# DigitalOutLED-02.net
KiCad netlist of a schematic drawn in EAGLE
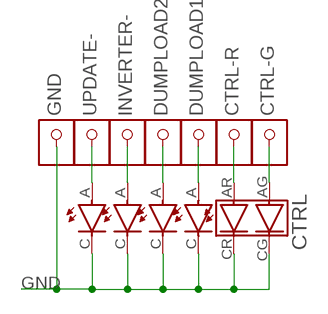
[diagram p0: schematic, sheet 1]

(export (version "E")
  (design (tool "Eeschema 10.0.6"))
  (components
    (comp (ref "CTRL")
      (value "PLCC4-RG")
      (footprint "eagle-import:PLCC4")
      (libsource (lib "eagle-import") (part "PLCC4-RG"))
    )
    (comp (ref "CTRL-G")
      (value "1X1HEADER")
      (footprint "eagle-import:1X1HEADER")
      (libsource (lib "eagle-import") (part "1X1HEADER"))
    )
    (comp (ref "CTRL-R")
      (value "1X1HEADER")
      (footprint "eagle-import:1X1HEADER")
      (libsource (lib "eagle-import") (part "1X1HEADER"))
    )
    (comp (ref "DL1")
      (value "PLCC2")
      (footprint "eagle-import:PLCC2")
      (libsource (lib "eagle-import") (part "PLCC2"))
    )
    (comp (ref "DL2")
      (value "PLCC2")
      (footprint "eagle-import:PLCC2")
      (libsource (lib "eagle-import") (part "PLCC2"))
    )
    (comp (ref "DUMPLOAD1")
      (value "1X1HEADER")
      (footprint "eagle-import:1X1HEADER")
      (libsource (lib "eagle-import") (part "1X1HEADER"))
    )
    (comp (ref "DUMPLOAD2")
      (value "1X1HEADER")
      (footprint "eagle-import:1X1HEADER")
      (libsource (lib "eagle-import") (part "1X1HEADER"))
    )
    (comp (ref "GND")
      (value "1X1HEADER")
      (footprint "eagle-import:1X1HEADER")
      (libsource (lib "eagle-import") (part "1X1HEADER"))
    )
    (comp (ref "INVERTER")
      (value "PLCC2")
      (footprint "eagle-import:PLCC2")
      (libsource (lib "eagle-import") (part "PLCC2"))
    )
    (comp (ref "INVERTER-")
      (value "1X1HEADER")
      (footprint "eagle-import:1X1HEADER")
      (libsource (lib "eagle-import") (part "1X1HEADER"))
    )
    (comp (ref "UPDATE")
      (value "PLCC2")
      (footprint "eagle-import:PLCC2")
      (libsource (lib "eagle-import") (part "PLCC2"))
    )
    (comp (ref "UPDATE-")
      (value "1X1HEADER")
      (footprint "eagle-import:1X1HEADER")
      (libsource (lib "eagle-import") (part "1X1HEADER"))
    )
  )
  (nets
    (net (code "1") (name "/GND") (class "Default")
      (node (ref "CTRL") (pin "CG") (pinfunction "CG_CG") (pintype "bidirectional"))
      (node (ref "CTRL") (pin "CR") (pinfunction "CR_CR") (pintype "bidirectional"))
      (node (ref "DL1") (pin "C") (pinfunction "C_C") (pintype "bidirectional"))
      (node (ref "DL2") (pin "C") (pinfunction "C_C") (pintype "bidirectional"))
      (node (ref "GND") (pin "P$1") (pinfunction "1_P$1") (pintype "bidirectional"))
      (node (ref "INVERTER") (pin "C") (pinfunction "C_C") (pintype "bidirectional"))
      (node (ref "UPDATE") (pin "C") (pinfunction "C_C") (pintype "bidirectional"))
    )
    (net (code "2") (name "Net-(CTRL-G-1)") (class "Default")
      (node (ref "CTRL") (pin "AG") (pinfunction "AG_AG") (pintype "bidirectional"))
      (node (ref "CTRL-G") (pin "P$1") (pinfunction "1_P$1") (pintype "bidirectional"))
    )
    (net (code "3") (name "Net-(CTRL-R-1)") (class "Default")
      (node (ref "CTRL") (pin "AR") (pinfunction "AR_AR") (pintype "bidirectional"))
      (node (ref "CTRL-R") (pin "P$1") (pinfunction "1_P$1") (pintype "bidirectional"))
    )
    (net (code "4") (name "Net-(DUMPLOAD1-1)") (class "Default")
      (node (ref "DL1") (pin "A") (pinfunction "A_A") (pintype "bidirectional"))
      (node (ref "DUMPLOAD1") (pin "P$1") (pinfunction "1_P$1") (pintype "bidirectional"))
    )
    (net (code "5") (name "Net-(DUMPLOAD2-1)") (class "Default")
      (node (ref "DL2") (pin "A") (pinfunction "A_A") (pintype "bidirectional"))
      (node (ref "DUMPLOAD2") (pin "P$1") (pinfunction "1_P$1") (pintype "bidirectional"))
    )
    (net (code "6") (name "Net-(INVERTER--1)") (class "Default")
      (node (ref "INVERTER") (pin "A") (pinfunction "A_A") (pintype "bidirectional"))
      (node (ref "INVERTER-") (pin "P$1") (pinfunction "1_P$1") (pintype "bidirectional"))
    )
    (net (code "7") (name "Net-(UPDATE--1)") (class "Default")
      (node (ref "UPDATE") (pin "A") (pinfunction "A_A") (pintype "bidirectional"))
      (node (ref "UPDATE-") (pin "P$1") (pinfunction "1_P$1") (pintype "bidirectional"))
    )
  )
)
